# module.net
KiCad netlist of a schematic drawn in EAGLE
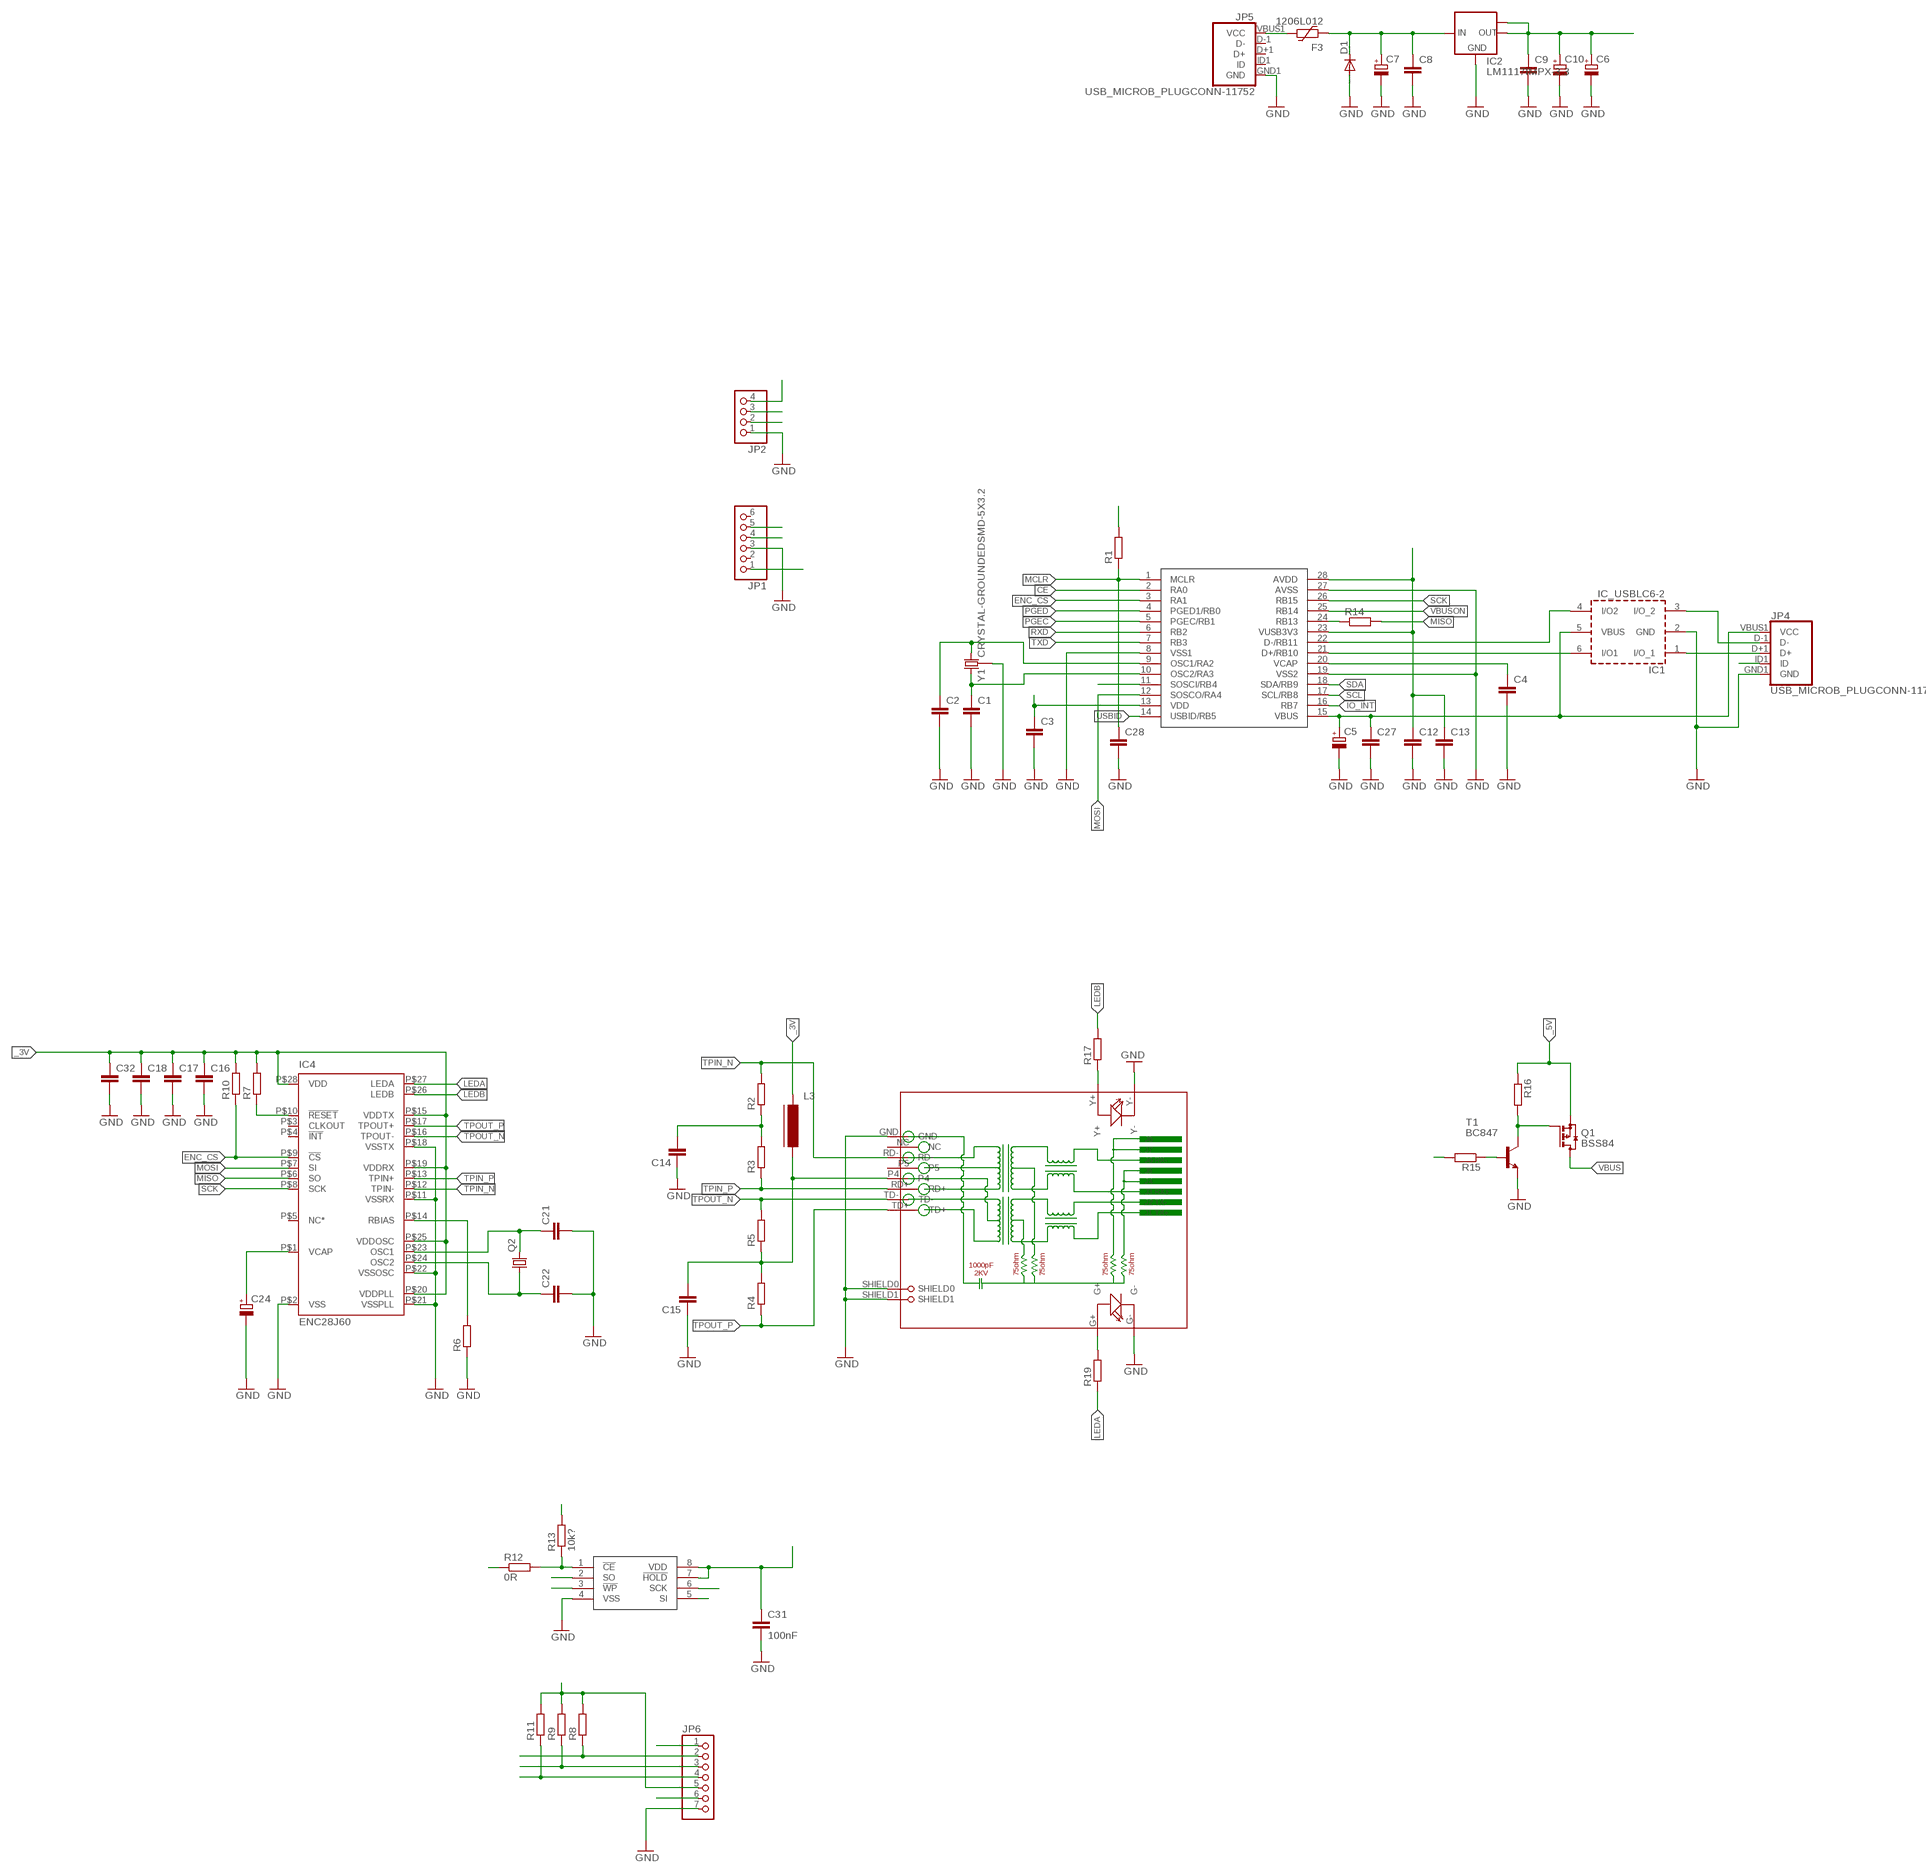
[diagram p0: schematic, sheet 1]

(export (version "E")
  (design (tool "Eeschema 10.0.6"))
  (components
    (comp (ref "C1")
      (value "C-EUC0603")
      (footprint "eagle-import:C0603")
      (libsource (lib "eagle-import") (part "C-EUC0603"))
    )
    (comp (ref "C2")
      (value "C-EUC0603")
      (footprint "eagle-import:C0603")
      (libsource (lib "eagle-import") (part "C-EUC0603"))
    )
    (comp (ref "C3")
      (value "C-EUC0402")
      (footprint "eagle-import:C0402")
      (libsource (lib "eagle-import") (part "C-EUC0402"))
    )
    (comp (ref "C4")
      (value "C-EUC0603")
      (footprint "eagle-import:C0603")
      (libsource (lib "eagle-import") (part "C-EUC0603"))
    )
    (comp (ref "C5")
      (value "CPOL-EUSMCA")
      (footprint "eagle-import:SMC_A")
      (libsource (lib "eagle-import") (part "CPOL-EUSMCA"))
    )
    (comp (ref "C6")
      (value "CPOL-EUSMCA")
      (footprint "eagle-import:SMC_A")
      (libsource (lib "eagle-import") (part "CPOL-EUSMCA"))
    )
    (comp (ref "C7")
      (value "CPOL-EUSMCC")
      (footprint "eagle-import:SMC_C")
      (libsource (lib "eagle-import") (part "CPOL-EUSMCC"))
    )
    (comp (ref "C8")
      (value "C-EUC0603")
      (footprint "eagle-import:C0603")
      (libsource (lib "eagle-import") (part "C-EUC0603"))
    )
    (comp (ref "C9")
      (value "C-EUC0603")
      (footprint "eagle-import:C0603")
      (libsource (lib "eagle-import") (part "C-EUC0603"))
    )
    (comp (ref "C10")
      (value "CPOL-EUSMCB")
      (footprint "eagle-import:SMC_B")
      (libsource (lib "eagle-import") (part "CPOL-EUSMCB"))
    )
    (comp (ref "C12")
      (value "C-EUC0402")
      (footprint "eagle-import:C0402")
      (libsource (lib "eagle-import") (part "C-EUC0402"))
    )
    (comp (ref "C13")
      (value "C-EUC0603")
      (footprint "eagle-import:C0603")
      (libsource (lib "eagle-import") (part "C-EUC0603"))
    )
    (comp (ref "C14")
      (value "C-EUC0603")
      (footprint "eagle-import:C0603")
      (libsource (lib "eagle-import") (part "C-EUC0603"))
    )
    (comp (ref "C15")
      (value "C-EUC0603")
      (footprint "eagle-import:C0603")
      (libsource (lib "eagle-import") (part "C-EUC0603"))
    )
    (comp (ref "C16")
      (value "C-EUC0402")
      (footprint "eagle-import:C0402")
      (libsource (lib "eagle-import") (part "C-EUC0402"))
    )
    (comp (ref "C17")
      (value "C-EUC0603")
      (footprint "eagle-import:C0603")
      (libsource (lib "eagle-import") (part "C-EUC0603"))
    )
    (comp (ref "C18")
      (value "C-EUC0603")
      (footprint "eagle-import:C0603")
      (libsource (lib "eagle-import") (part "C-EUC0603"))
    )
    (comp (ref "C21")
      (value "C-EUC0603")
      (footprint "eagle-import:C0603")
      (libsource (lib "eagle-import") (part "C-EUC0603"))
    )
    (comp (ref "C22")
      (value "C-EUC0603")
      (footprint "eagle-import:C0603")
      (libsource (lib "eagle-import") (part "C-EUC0603"))
    )
    (comp (ref "C24")
      (value "CPOL-EUSMCA")
      (footprint "eagle-import:SMC_A")
      (libsource (lib "eagle-import") (part "CPOL-EUSMCA"))
    )
    (comp (ref "C27")
      (value "C-EUC0603")
      (footprint "eagle-import:C0603")
      (libsource (lib "eagle-import") (part "C-EUC0603"))
    )
    (comp (ref "C28")
      (value "C-EUC0603")
      (footprint "eagle-import:C0603")
      (libsource (lib "eagle-import") (part "C-EUC0603"))
    )
    (comp (ref "C31")
      (value "100nF")
      (footprint "eagle-import:C0603")
      (libsource (lib "eagle-import") (part "C-EUC0603"))
    )
    (comp (ref "C32")
      (value "C-EUC0402")
      (footprint "eagle-import:C0402")
      (libsource (lib "eagle-import") (part "C-EUC0402"))
    )
    (comp (ref "D1")
      (value "DIODE-SMB")
      (footprint "eagle-import:SMB")
      (libsource (lib "eagle-import") (part "DIODE-SMB"))
    )
    (comp (ref "F3")
      (value "1206L012")
      (footprint "eagle-import:1206L")
      (fields (field (name "MF") "Littelfuse"))
      (libsource (lib "eagle-import") (part "?1206L012"))
    )
    (comp (ref "IC1")
      (value "IC_USBLC6-2")
      (footprint "eagle-import:SOT-23-6L")
      (libsource (lib "eagle-import") (part "IC_USBLC6-2"))
    )
    (comp (ref "IC2")
      (value "LM1117IMPX-3.3")
      (footprint "eagle-import:SOT223")
      (libsource (lib "eagle-import") (part "LM1117IMPX-3.3"))
    )
    (comp (ref "IC4")
      (value "ENC28J60")
      (footprint "eagle-import:TSSOP28W")
      (libsource (lib "eagle-import") (part "ENC28J60"))
    )
    (comp (ref "JP1")
      (value "PINHD-1X6")
      (footprint "eagle-import:1X06")
      (libsource (lib "eagle-import") (part "PINHD-1X6"))
    )
    (comp (ref "JP2")
      (value "PINHD-1X4")
      (footprint "eagle-import:1X04")
      (libsource (lib "eagle-import") (part "PINHD-1X4"))
    )
    (comp (ref "JP4")
      (value "USB_MICROB_PLUGCONN-11752")
      (footprint "eagle-import:USB-B-MICRO-SMD_V03")
      (libsource (lib "eagle-import") (part "USB_MICROB_PLUGCONN-11752"))
    )
    (comp (ref "JP5")
      (value "USB_MICROB_PLUGCONN-11752")
      (footprint "eagle-import:USB-B-MICRO-SMD_V03")
      (libsource (lib "eagle-import") (part "USB_MICROB_PLUGCONN-11752"))
    )
    (comp (ref "JP6")
      (value "PINHD-1X7")
      (footprint "eagle-import:1X07")
      (libsource (lib "eagle-import") (part "PINHD-1X7"))
    )
    (comp (ref "L3")
      (value "FERRITE-0805")
      (footprint "eagle-import:FB805")
      (libsource (lib "eagle-import") (part "FERRITE-0805"))
    )
    (comp (ref "Q1")
      (value "BSS84")
      (footprint "eagle-import:SOT23")
      (libsource (lib "eagle-import") (part "BSS84"))
    )
    (comp (ref "Q2")
      (value "CRYSTALHC49S")
      (footprint "eagle-import:HC49_S")
      (libsource (lib "eagle-import") (part "CRYSTALHC49S"))
    )
    (comp (ref "R1")
      (value "R-EU_R0603")
      (footprint "eagle-import:R0603")
      (libsource (lib "eagle-import") (part "R-EU_R0603"))
    )
    (comp (ref "R2")
      (value "R-EU_R0603")
      (footprint "eagle-import:R0603")
      (libsource (lib "eagle-import") (part "R-EU_R0603"))
    )
    (comp (ref "R3")
      (value "R-EU_R0603")
      (footprint "eagle-import:R0603")
      (libsource (lib "eagle-import") (part "R-EU_R0603"))
    )
    (comp (ref "R4")
      (value "R-EU_R0603")
      (footprint "eagle-import:R0603")
      (libsource (lib "eagle-import") (part "R-EU_R0603"))
    )
    (comp (ref "R5")
      (value "R-EU_R0603")
      (footprint "eagle-import:R0603")
      (libsource (lib "eagle-import") (part "R-EU_R0603"))
    )
    (comp (ref "R6")
      (value "R-EU_R0805")
      (footprint "eagle-import:R0805")
      (libsource (lib "eagle-import") (part "R-EU_R0805"))
    )
    (comp (ref "R7")
      (value "R-EU_R0402")
      (footprint "eagle-import:R0402")
      (libsource (lib "eagle-import") (part "R-EU_R0402"))
    )
    (comp (ref "R8")
      (value "R-EU_R0603")
      (footprint "eagle-import:R0603")
      (libsource (lib "eagle-import") (part "R-EU_R0603"))
    )
    (comp (ref "R9")
      (value "R-EU_R0603")
      (footprint "eagle-import:R0603")
      (libsource (lib "eagle-import") (part "R-EU_R0603"))
    )
    (comp (ref "R10")
      (value "R-EU_R0402")
      (footprint "eagle-import:R0402")
      (libsource (lib "eagle-import") (part "R-EU_R0402"))
    )
    (comp (ref "R11")
      (value "R-EU_R0603")
      (footprint "eagle-import:R0603")
      (libsource (lib "eagle-import") (part "R-EU_R0603"))
    )
    (comp (ref "R12")
      (value "0R")
      (footprint "eagle-import:R0603")
      (libsource (lib "eagle-import") (part "R-EU_R0603"))
    )
    (comp (ref "R13")
      (value "10k?")
      (footprint "eagle-import:R0603")
      (libsource (lib "eagle-import") (part "R-EU_R0603"))
    )
    (comp (ref "R14")
      (value "R-EU_R0603")
      (footprint "eagle-import:R0603")
      (libsource (lib "eagle-import") (part "R-EU_R0603"))
    )
    (comp (ref "R15")
      (value "R-EU_R0603")
      (footprint "eagle-import:R0603")
      (libsource (lib "eagle-import") (part "R-EU_R0603"))
    )
    (comp (ref "R16")
      (value "R-EU_R0603")
      (footprint "eagle-import:R0603")
      (libsource (lib "eagle-import") (part "R-EU_R0603"))
    )
    (comp (ref "R17")
      (value "R-EU_R1206")
      (footprint "eagle-import:R1206")
      (libsource (lib "eagle-import") (part "R-EU_R1206"))
    )
    (comp (ref "R19")
      (value "R-EU_R1206")
      (footprint "eagle-import:R1206")
      (libsource (lib "eagle-import") (part "R-EU_R1206"))
    )
    (comp (ref "RJ1")
      (value "HR911105A")
      (footprint "eagle-import:HR911105A")
      (libsource (lib "eagle-import") (part "HR911105A"))
    )
    (comp (ref "T1")
      (value "BC847")
      (footprint "eagle-import:SOT23")
      (libsource (lib "eagle-import") (part "BC847"))
    )
    (comp (ref "U$1")
      (value "PIC32MX250F128B2")
      (footprint "eagle-import:SSOP28")
      (libsource (lib "eagle-import") (part "PIC32MX250F128B2"))
    )
    (comp (ref "U$2")
      (value "SST25VF016BSO8M")
      (footprint "eagle-import:SO-08M")
      (libsource (lib "eagle-import") (part "SST25VF016BSO8M"))
    )
    (comp (ref "Y1")
      (value "CRYSTAL-GROUNDEDSMD-5X3.2")
      (footprint "eagle-import:CRYSTAL-SMD-5X3.2-4PAD")
      (libsource (lib "eagle-import") (part "CRYSTAL-GROUNDEDSMD-5X3.2"))
    )
  )
  (nets
    (net (code "1") (name "/SIG") (class "Default")
      (node (ref "JP6") (pin "6") (pinfunction "6_6") (pintype "passive"))
      (node (ref "U$1") (pin "11") (pinfunction "SOSCI/RB4_11") (pintype "bidirectional"))
    )
    (net (code "2") (name "CE") (class "Default")
      (node (ref "R12") (pin "1") (pinfunction "1_1") (pintype "passive"))
      (node (ref "U$1") (pin "2") (pinfunction "RA0_2") (pintype "bidirectional"))
    )
    (net (code "3") (name "ENC_CS") (class "Default")
      (node (ref "IC4") (pin "P$9") (pinfunction "~{CS}_P$9") (pintype "input"))
      (node (ref "R10") (pin "1") (pinfunction "1_1") (pintype "passive"))
      (node (ref "U$1") (pin "3") (pinfunction "RA1_3") (pintype "bidirectional"))
    )
    (net (code "4") (name "GND") (class "Default")
      (node (ref "C1") (pin "2") (pinfunction "2_2") (pintype "passive"))
      (node (ref "C10") (pin "-") (pinfunction "-_-") (pintype "passive"))
      (node (ref "C12") (pin "2") (pinfunction "2_2") (pintype "passive"))
      (node (ref "C13") (pin "2") (pinfunction "2_2") (pintype "passive"))
      (node (ref "C14") (pin "1") (pinfunction "1_1") (pintype "passive"))
      (node (ref "C15") (pin "1") (pinfunction "1_1") (pintype "passive"))
      (node (ref "C16") (pin "2") (pinfunction "2_2") (pintype "passive"))
      (node (ref "C17") (pin "2") (pinfunction "2_2") (pintype "passive"))
      (node (ref "C18") (pin "2") (pinfunction "2_2") (pintype "passive"))
      (node (ref "C2") (pin "2") (pinfunction "2_2") (pintype "passive"))
      (node (ref "C21") (pin "2") (pinfunction "2_2") (pintype "passive"))
      (node (ref "C22") (pin "2") (pinfunction "2_2") (pintype "passive"))
      (node (ref "C24") (pin "-") (pinfunction "-_-") (pintype "passive"))
      (node (ref "C27") (pin "2") (pinfunction "2_2") (pintype "passive"))
      (node (ref "C28") (pin "2") (pinfunction "2_2") (pintype "passive"))
      (node (ref "C3") (pin "2") (pinfunction "2_2") (pintype "passive"))
      (node (ref "C31") (pin "2") (pinfunction "2_2") (pintype "passive"))
      (node (ref "C32") (pin "2") (pinfunction "2_2") (pintype "passive"))
      (node (ref "C4") (pin "2") (pinfunction "2_2") (pintype "passive"))
      (node (ref "C5") (pin "-") (pinfunction "-_-") (pintype "passive"))
      (node (ref "C6") (pin "-") (pinfunction "-_-") (pintype "passive"))
      (node (ref "C7") (pin "-") (pinfunction "-_-") (pintype "passive"))
      (node (ref "C8") (pin "2") (pinfunction "2_2") (pintype "passive"))
      (node (ref "C9") (pin "2") (pinfunction "2_2") (pintype "passive"))
      (node (ref "D1") (pin "A") (pinfunction "A_A") (pintype "passive"))
      (node (ref "IC1") (pin "2") (pinfunction "GND_2") (pintype "bidirectional"))
      (node (ref "IC2") (pin "1") (pinfunction "GND_1") (pintype "input"))
      (node (ref "IC4") (pin "P$11") (pinfunction "VSSRX_P$11") (pintype "input"))
      (node (ref "IC4") (pin "P$18") (pinfunction "VSSTX_P$18") (pintype "input"))
      (node (ref "IC4") (pin "P$2") (pinfunction "VSS_P$2") (pintype "input"))
      (node (ref "IC4") (pin "P$21") (pinfunction "VSSPLL_P$21") (pintype "input"))
      (node (ref "IC4") (pin "P$22") (pinfunction "VSSOSC_P$22") (pintype "input"))
      (node (ref "JP1") (pin "3") (pinfunction "3_3") (pintype "passive"))
      (node (ref "JP2") (pin "1") (pinfunction "1_1") (pintype "passive"))
      (node (ref "JP4") (pin "GND1") (pinfunction "GND_GND1") (pintype "bidirectional"))
      (node (ref "JP5") (pin "GND1") (pinfunction "GND_GND1") (pintype "bidirectional"))
      (node (ref "JP6") (pin "7") (pinfunction "7_7") (pintype "passive"))
      (node (ref "R6") (pin "1") (pinfunction "1_1") (pintype "passive"))
      (node (ref "RJ1") (pin "G-") (pinfunction "G-_G-") (pintype "bidirectional"))
      (node (ref "RJ1") (pin "GND") (pinfunction "GND_GND") (pintype "bidirectional"))
      (node (ref "RJ1") (pin "SHIELD0") (pinfunction "SHIELD0_SHIELD0") (pintype "bidirectional"))
      (node (ref "RJ1") (pin "SHIELD1") (pinfunction "SHIELD1_SHIELD1") (pintype "bidirectional"))
      (node (ref "RJ1") (pin "Y-") (pinfunction "Y-_Y-") (pintype "bidirectional"))
      (node (ref "T1") (pin "2") (pinfunction "E_2") (pintype "passive"))
      (node (ref "U$1") (pin "19") (pinfunction "VSS2_19") (pintype "bidirectional"))
      (node (ref "U$1") (pin "27") (pinfunction "AVSS_27") (pintype "bidirectional"))
      (node (ref "U$1") (pin "8") (pinfunction "VSS1_8") (pintype "bidirectional"))
      (node (ref "U$2") (pin "4") (pinfunction "VSS_4") (pintype "bidirectional"))
      (node (ref "Y1") (pin "2") (pinfunction "3_2") (pintype "passive"))
      (node (ref "Y1") (pin "4") (pinfunction "3_4") (pintype "passive"))
    )
    (net (code "5") (name "IO_INT") (class "Default")
      (node (ref "JP6") (pin "2") (pinfunction "2_2") (pintype "passive"))
      (node (ref "R8") (pin "1") (pinfunction "1_1") (pintype "passive"))
      (node (ref "U$1") (pin "16") (pinfunction "RB7_16") (pintype "bidirectional"))
    )
    (net (code "6") (name "LEDA") (class "Default")
      (node (ref "IC4") (pin "P$27") (pinfunction "LEDA_P$27") (pintype "output"))
      (node (ref "R19") (pin "1") (pinfunction "1_1") (pintype "passive"))
    )
    (net (code "7") (name "LEDB") (class "Default")
      (node (ref "IC4") (pin "P$26") (pinfunction "LEDB_P$26") (pintype "output"))
      (node (ref "R17") (pin "2") (pinfunction "2_2") (pintype "passive"))
    )
    (net (code "8") (name "MCLR") (class "Default")
      (node (ref "C28") (pin "1") (pinfunction "1_1") (pintype "passive"))
      (node (ref "JP1") (pin "1") (pinfunction "1_1") (pintype "passive"))
      (node (ref "R1") (pin "1") (pinfunction "1_1") (pintype "passive"))
      (node (ref "U$1") (pin "1") (pinfunction "MCLR_1") (pintype "bidirectional"))
    )
    (net (code "9") (name "MISO") (class "Default")
      (node (ref "IC4") (pin "P$6") (pinfunction "SO_P$6") (pintype "output"))
      (node (ref "R14") (pin "2") (pinfunction "2_2") (pintype "passive"))
      (node (ref "U$2") (pin "2") (pinfunction "SO_2") (pintype "bidirectional"))
    )
    (net (code "10") (name "MOSI") (class "Default")
      (node (ref "IC4") (pin "P$7") (pinfunction "SI_P$7") (pintype "input"))
      (node (ref "U$1") (pin "12") (pinfunction "SOSCO/RA4_12") (pintype "bidirectional"))
      (node (ref "U$2") (pin "5") (pinfunction "SI_5") (pintype "bidirectional"))
    )
    (net (code "11") (name "Net-(C14-Pad2)") (class "Default")
      (node (ref "C14") (pin "2") (pinfunction "2_2") (pintype "passive"))
      (node (ref "R2") (pin "1") (pinfunction "1_1") (pintype "passive"))
      (node (ref "R3") (pin "2") (pinfunction "2_2") (pintype "passive"))
    )
    (net (code "12") (name "Net-(C15-Pad2)") (class "Default")
      (node (ref "C15") (pin "2") (pinfunction "2_2") (pintype "passive"))
      (node (ref "L3") (pin "2") (pinfunction "2_2") (pintype "passive"))
      (node (ref "R4") (pin "2") (pinfunction "2_2") (pintype "passive"))
      (node (ref "R5") (pin "1") (pinfunction "1_1") (pintype "passive"))
      (node (ref "RJ1") (pin "P4") (pinfunction "P4_P4") (pintype "bidirectional"))
    )
    (net (code "13") (name "Net-(IC1-I{slash}O1)") (class "Default")
      (node (ref "IC1") (pin "6") (pinfunction "I/O1_6") (pintype "bidirectional"))
      (node (ref "U$1") (pin "21") (pinfunction "D+/RB10_21") (pintype "bidirectional"))
    )
    (net (code "14") (name "Net-(IC1-I{slash}O2)") (class "Default")
      (node (ref "IC1") (pin "4") (pinfunction "I/O2_4") (pintype "bidirectional"))
      (node (ref "U$1") (pin "22") (pinfunction "D-/RB11_22") (pintype "bidirectional"))
    )
    (net (code "15") (name "Net-(IC1-I{slash}O_1)") (class "Default")
      (node (ref "IC1") (pin "1") (pinfunction "I/O_1_1") (pintype "bidirectional"))
      (node (ref "JP4") (pin "D+1") (pinfunction "D+_D+1") (pintype "bidirectional"))
    )
    (net (code "16") (name "Net-(IC1-I{slash}O_2)") (class "Default")
      (node (ref "IC1") (pin "3") (pinfunction "I/O_2_3") (pintype "bidirectional"))
      (node (ref "JP4") (pin "D-1") (pinfunction "D-_D-1") (pintype "bidirectional"))
    )
    (net (code "17") (name "Net-(IC4-OSC1)") (class "Default")
      (node (ref "C21") (pin "1") (pinfunction "1_1") (pintype "passive"))
      (node (ref "IC4") (pin "P$23") (pinfunction "OSC1_P$23") (pintype "input"))
      (node (ref "Q2") (pin "2") (pinfunction "2_2") (pintype "passive"))
    )
    (net (code "18") (name "Net-(IC4-OSC2)") (class "Default")
      (node (ref "C22") (pin "1") (pinfunction "1_1") (pintype "passive"))
      (node (ref "IC4") (pin "P$24") (pinfunction "OSC2_P$24") (pintype "output"))
      (node (ref "Q2") (pin "1") (pinfunction "1_1") (pintype "passive"))
    )
    (net (code "19") (name "Net-(IC4-RBIAS)") (class "Default")
      (node (ref "IC4") (pin "P$14") (pinfunction "RBIAS_P$14") (pintype "input"))
      (node (ref "R6") (pin "2") (pinfunction "2_2") (pintype "passive"))
    )
    (net (code "20") (name "Net-(IC4-VCAP)") (class "Default")
      (node (ref "C24") (pin "+") (pinfunction "+_+") (pintype "passive"))
      (node (ref "IC4") (pin "P$1") (pinfunction "VCAP_P$1") (pintype "input"))
    )
    (net (code "21") (name "Net-(IC4-~{RESET})") (class "Default")
      (node (ref "IC4") (pin "P$10") (pinfunction "~{RESET}_P$10") (pintype "input"))
      (node (ref "R7") (pin "1") (pinfunction "1_1") (pintype "passive"))
    )
    (net (code "22") (name "Net-(JP5-VCC)") (class "Default")
      (node (ref "F3") (pin "1") (pinfunction "1_1") (pintype "passive"))
      (node (ref "JP5") (pin "VBUS1") (pinfunction "VCC_VBUS1") (pintype "bidirectional"))
    )
    (net (code "23") (name "Net-(Q1-G)") (class "Default")
      (node (ref "Q1") (pin "1") (pinfunction "G_1") (pintype "passive"))
      (node (ref "R16") (pin "2") (pinfunction "2_2") (pintype "passive"))
      (node (ref "T1") (pin "3") (pinfunction "C_3") (pintype "passive"))
    )
    (net (code "24") (name "Net-(R17-Pad1)") (class "Default")
      (node (ref "R17") (pin "1") (pinfunction "1_1") (pintype "passive"))
      (node (ref "RJ1") (pin "Y+") (pinfunction "Y+_Y+") (pintype "bidirectional"))
    )
    (net (code "25") (name "Net-(R19-Pad2)") (class "Default")
      (node (ref "R19") (pin "2") (pinfunction "2_2") (pintype "passive"))
      (node (ref "RJ1") (pin "G+") (pinfunction "G+_G+") (pintype "bidirectional"))
    )
    (net (code "26") (name "Net-(T1-B)") (class "Default")
      (node (ref "R15") (pin "1") (pinfunction "1_1") (pintype "passive"))
      (node (ref "T1") (pin "1") (pinfunction "B_1") (pintype "passive"))
    )
    (net (code "27") (name "Net-(U$1-OSC1{slash}RA2)") (class "Default")
      (node (ref "C2") (pin "1") (pinfunction "1_1") (pintype "passive"))
      (node (ref "U$1") (pin "9") (pinfunction "OSC1/RA2_9") (pintype "bidirectional"))
      (node (ref "Y1") (pin "1") (pinfunction "2_1") (pintype "passive"))
    )
    (net (code "28") (name "Net-(U$1-OSC2{slash}RA3)") (class "Default")
      (node (ref "C1") (pin "1") (pinfunction "1_1") (pintype "passive"))
      (node (ref "U$1") (pin "10") (pinfunction "OSC2/RA3_10") (pintype "bidirectional"))
      (node (ref "Y1") (pin "3") (pinfunction "1_3") (pintype "passive"))
    )
    (net (code "29") (name "Net-(U$1-RB13)") (class "Default")
      (node (ref "R14") (pin "1") (pinfunction "1_1") (pintype "passive"))
      (node (ref "U$1") (pin "24") (pinfunction "RB13_24") (pintype "bidirectional"))
    )
    (net (code "30") (name "Net-(U$1-VCAP)") (class "Default")
      (node (ref "C4") (pin "1") (pinfunction "1_1") (pintype "passive"))
      (node (ref "U$1") (pin "20") (pinfunction "VCAP_20") (pintype "bidirectional"))
    )
    (net (code "31") (name "Net-(U$2-~{CE})") (class "Default")
      (node (ref "R12") (pin "2") (pinfunction "2_2") (pintype "passive"))
      (node (ref "R13") (pin "1") (pinfunction "1_1") (pintype "passive"))
      (node (ref "U$2") (pin "1") (pinfunction "~{CE}_1") (pintype "bidirectional"))
    )
    (net (code "32") (name "PGEC") (class "Default")
      (node (ref "JP1") (pin "5") (pinfunction "5_5") (pintype "passive"))
      (node (ref "U$1") (pin "5") (pinfunction "PGEC/RB1_5") (pintype "bidirectional"))
    )
    (net (code "33") (name "PGED") (class "Default")
      (node (ref "JP1") (pin "4") (pinfunction "4_4") (pintype "passive"))
      (node (ref "U$1") (pin "4") (pinfunction "PGED1/RB0_4") (pintype "bidirectional"))
    )
    (net (code "34") (name "RXD") (class "Default")
      (node (ref "JP2") (pin "3") (pinfunction "3_3") (pintype "passive"))
      (node (ref "U$1") (pin "6") (pinfunction "RB2_6") (pintype "bidirectional"))
    )
    (net (code "35") (name "SCK") (class "Default")
      (node (ref "IC4") (pin "P$8") (pinfunction "SCK_P$8") (pintype "input"))
      (node (ref "U$1") (pin "26") (pinfunction "RB15_26") (pintype "bidirectional"))
      (node (ref "U$2") (pin "6") (pinfunction "SCK_6") (pintype "bidirectional"))
    )
    (net (code "36") (name "SCL") (class "Default")
      (node (ref "JP6") (pin "3") (pinfunction "3_3") (pintype "passive"))
      (node (ref "R9") (pin "1") (pinfunction "1_1") (pintype "passive"))
      (node (ref "U$1") (pin "17") (pinfunction "SCL/RB8_17") (pintype "bidirectional"))
    )
    (net (code "37") (name "SDA") (class "Default")
      (node (ref "JP6") (pin "4") (pinfunction "4_4") (pintype "passive"))
      (node (ref "R11") (pin "1") (pinfunction "1_1") (pintype "passive"))
      (node (ref "U$1") (pin "18") (pinfunction "SDA/RB9_18") (pintype "bidirectional"))
    )
    (net (code "38") (name "TPIN_N") (class "Default")
      (node (ref "IC4") (pin "P$12") (pinfunction "TPIN-_P$12") (pintype "input"))
      (node (ref "R2") (pin "2") (pinfunction "2_2") (pintype "passive"))
      (node (ref "RJ1") (pin "RD-") (pinfunction "RD-_RD-") (pintype "bidirectional"))
    )
    (net (code "39") (name "TPIN_P") (class "Default")
      (node (ref "IC4") (pin "P$13") (pinfunction "TPIN+_P$13") (pintype "input"))
      (node (ref "R3") (pin "1") (pinfunction "1_1") (pintype "passive"))
      (node (ref "RJ1") (pin "RD+") (pinfunction "RD+_RD+") (pintype "bidirectional"))
    )
    (net (code "40") (name "TPOUT_N") (class "Default")
      (node (ref "IC4") (pin "P$16") (pinfunction "TPOUT-_P$16") (pintype "output"))
      (node (ref "R5") (pin "2") (pinfunction "2_2") (pintype "passive"))
      (node (ref "RJ1") (pin "TD-") (pinfunction "TD-_TD-") (pintype "bidirectional"))
    )
    (net (code "41") (name "TPOUT_P") (class "Default")
      (node (ref "IC4") (pin "P$17") (pinfunction "TPOUT+_P$17") (pintype "output"))
      (node (ref "R4") (pin "1") (pinfunction "1_1") (pintype "passive"))
      (node (ref "RJ1") (pin "TD+") (pinfunction "TD+_TD+") (pintype "bidirectional"))
    )
    (net (code "42") (name "TXD") (class "Default")
      (node (ref "JP2") (pin "2") (pinfunction "2_2") (pintype "passive"))
      (node (ref "U$1") (pin "7") (pinfunction "RB3_7") (pintype "bidirectional"))
    )
    (net (code "43") (name "USBID") (class "Default")
      (node (ref "JP4") (pin "ID1") (pinfunction "ID_ID1") (pintype "bidirectional"))
      (node (ref "U$1") (pin "14") (pinfunction "USBID/RB5_14") (pintype "bidirectional"))
    )
    (net (code "44") (name "VBUS") (class "Default")
      (node (ref "C27") (pin "1") (pinfunction "1_1") (pintype "passive"))
      (node (ref "C5") (pin "+") (pinfunction "+_+") (pintype "passive"))
      (node (ref "IC1") (pin "5") (pinfunction "VBUS_5") (pintype "bidirectional"))
      (node (ref "JP4") (pin "VBUS1") (pinfunction "VCC_VBUS1") (pintype "bidirectional"))
      (node (ref "Q1") (pin "3") (pinfunction "D_3") (pintype "passive"))
      (node (ref "U$1") (pin "15") (pinfunction "VBUS_15") (pintype "bidirectional"))
    )
    (net (code "45") (name "VBUSON") (class "Default")
      (node (ref "R15") (pin "2") (pinfunction "2_2") (pintype "passive"))
      (node (ref "U$1") (pin "25") (pinfunction "RB14_25") (pintype "bidirectional"))
    )
    (net (code "46") (name "_3V") (class "Default")
      (node (ref "C10") (pin "+") (pinfunction "+_+") (pintype "passive"))
      (node (ref "C12") (pin "1") (pinfunction "1_1") (pintype "passive"))
      (node (ref "C13") (pin "1") (pinfunction "1_1") (pintype "passive"))
      (node (ref "C16") (pin "1") (pinfunction "1_1") (pintype "passive"))
      (node (ref "C17") (pin "1") (pinfunction "1_1") (pintype "passive"))
      (node (ref "C18") (pin "1") (pinfunction "1_1") (pintype "passive"))
      (node (ref "C3") (pin "1") (pinfunction "1_1") (pintype "passive"))
      (node (ref "C31") (pin "1") (pinfunction "1_1") (pintype "passive"))
      (node (ref "C32") (pin "1") (pinfunction "1_1") (pintype "passive"))
      (node (ref "C6") (pin "+") (pinfunction "+_+") (pintype "passive"))
      (node (ref "C9") (pin "1") (pinfunction "1_1") (pintype "passive"))
      (node (ref "IC2") (pin "2") (pinfunction "OUT_2") (pintype "passive"))
      (node (ref "IC2") (pin "TAB") (pinfunction "OUT1_TAB") (pintype "passive"))
      (node (ref "IC4") (pin "P$15") (pinfunction "VDDTX_P$15") (pintype "input"))
      (node (ref "IC4") (pin "P$19") (pinfunction "VDDRX_P$19") (pintype "input"))
      (node (ref "IC4") (pin "P$20") (pinfunction "VDDPLL_P$20") (pintype "input"))
      (node (ref "IC4") (pin "P$25") (pinfunction "VDDOSC_P$25") (pintype "input"))
      (node (ref "IC4") (pin "P$28") (pinfunction "VDD_P$28") (pintype "input"))
      (node (ref "JP2") (pin "4") (pinfunction "4_4") (pintype "passive"))
      (node (ref "JP6") (pin "5") (pinfunction "5_5") (pintype "passive"))
      (node (ref "L3") (pin "1") (pinfunction "1_1") (pintype "passive"))
      (node (ref "R1") (pin "2") (pinfunction "2_2") (pintype "passive"))
      (node (ref "R10") (pin "2") (pinfunction "2_2") (pintype "passive"))
      (node (ref "R11") (pin "2") (pinfunction "2_2") (pintype "passive"))
      (node (ref "R13") (pin "2") (pinfunction "2_2") (pintype "passive"))
      (node (ref "R7") (pin "2") (pinfunction "2_2") (pintype "passive"))
      (node (ref "R8") (pin "2") (pinfunction "2_2") (pintype "passive"))
      (node (ref "R9") (pin "2") (pinfunction "2_2") (pintype "passive"))
      (node (ref "U$1") (pin "13") (pinfunction "VDD_13") (pintype "bidirectional"))
      (node (ref "U$1") (pin "23") (pinfunction "VUSB3V3_23") (pintype "bidirectional"))
      (node (ref "U$1") (pin "28") (pinfunction "AVDD_28") (pintype "bidirectional"))
      (node (ref "U$2") (pin "3") (pinfunction "~{WP}_3") (pintype "bidirectional"))
      (node (ref "U$2") (pin "7") (pinfunction "~{HOLD}_7") (pintype "bidirectional"))
      (node (ref "U$2") (pin "8") (pinfunction "VDD_8") (pintype "bidirectional"))
    )
    (net (code "47") (name "_5V") (class "Default")
      (node (ref "C7") (pin "+") (pinfunction "+_+") (pintype "passive"))
      (node (ref "C8") (pin "1") (pinfunction "1_1") (pintype "passive"))
      (node (ref "D1") (pin "C") (pinfunction "C_C") (pintype "passive"))
      (node (ref "F3") (pin "2") (pinfunction "2_2") (pintype "passive"))
      (node (ref "IC2") (pin "3") (pinfunction "IN_3") (pintype "input"))
      (node (ref "JP6") (pin "1") (pinfunction "1_1") (pintype "passive"))
      (node (ref "Q1") (pin "2") (pinfunction "S_2") (pintype "passive"))
      (node (ref "R16") (pin "1") (pinfunction "1_1") (pintype "passive"))
    )
    (net (code "48") (name "unconnected-(IC4-CLKOUT-PadP$3)") (class "Default")
      (node (ref "IC4") (pin "P$3") (pinfunction "CLKOUT_P$3") (pintype "output"))
    )
    (net (code "49") (name "unconnected-(IC4-NC*-PadP$5)") (class "Default")
      (node (ref "IC4") (pin "P$5") (pinfunction "NC*_P$5") (pintype "output"))
    )
    (net (code "50") (name "unconnected-(IC4-~{INT}-PadP$4)") (class "Default")
      (node (ref "IC4") (pin "P$4") (pinfunction "~{INT}_P$4") (pintype "output"))
    )
    (net (code "51") (name "unconnected-(JP1-Pad2)") (class "Default")
      (node (ref "JP1") (pin "2") (pinfunction "2_2") (pintype "passive"))
    )
    (net (code "52") (name "unconnected-(JP1-Pad6)") (class "Default")
      (node (ref "JP1") (pin "6") (pinfunction "6_6") (pintype "passive"))
    )
    (net (code "53") (name "unconnected-(JP5-D+-PadD+1)") (class "Default")
      (node (ref "JP5") (pin "D+1") (pinfunction "D+_D+1") (pintype "bidirectional"))
    )
    (net (code "54") (name "unconnected-(JP5-D--PadD-1)") (class "Default")
      (node (ref "JP5") (pin "D-1") (pinfunction "D-_D-1") (pintype "bidirectional"))
    )
    (net (code "55") (name "unconnected-(JP5-ID-PadID1)") (class "Default")
      (node (ref "JP5") (pin "ID1") (pinfunction "ID_ID1") (pintype "bidirectional"))
    )
    (net (code "56") (name "unconnected-(RJ1-PadNC)") (class "Default")
      (node (ref "RJ1") (pin "NC") (pinfunction "NC_NC") (pintype "bidirectional"))
    )
    (net (code "57") (name "unconnected-(RJ1-PadP5)") (class "Default")
      (node (ref "RJ1") (pin "P5") (pinfunction "P5_P5") (pintype "bidirectional"))
    )
  )
)
